# Sensors.net
KiCad netlist of a schematic drawn in Altium Designer
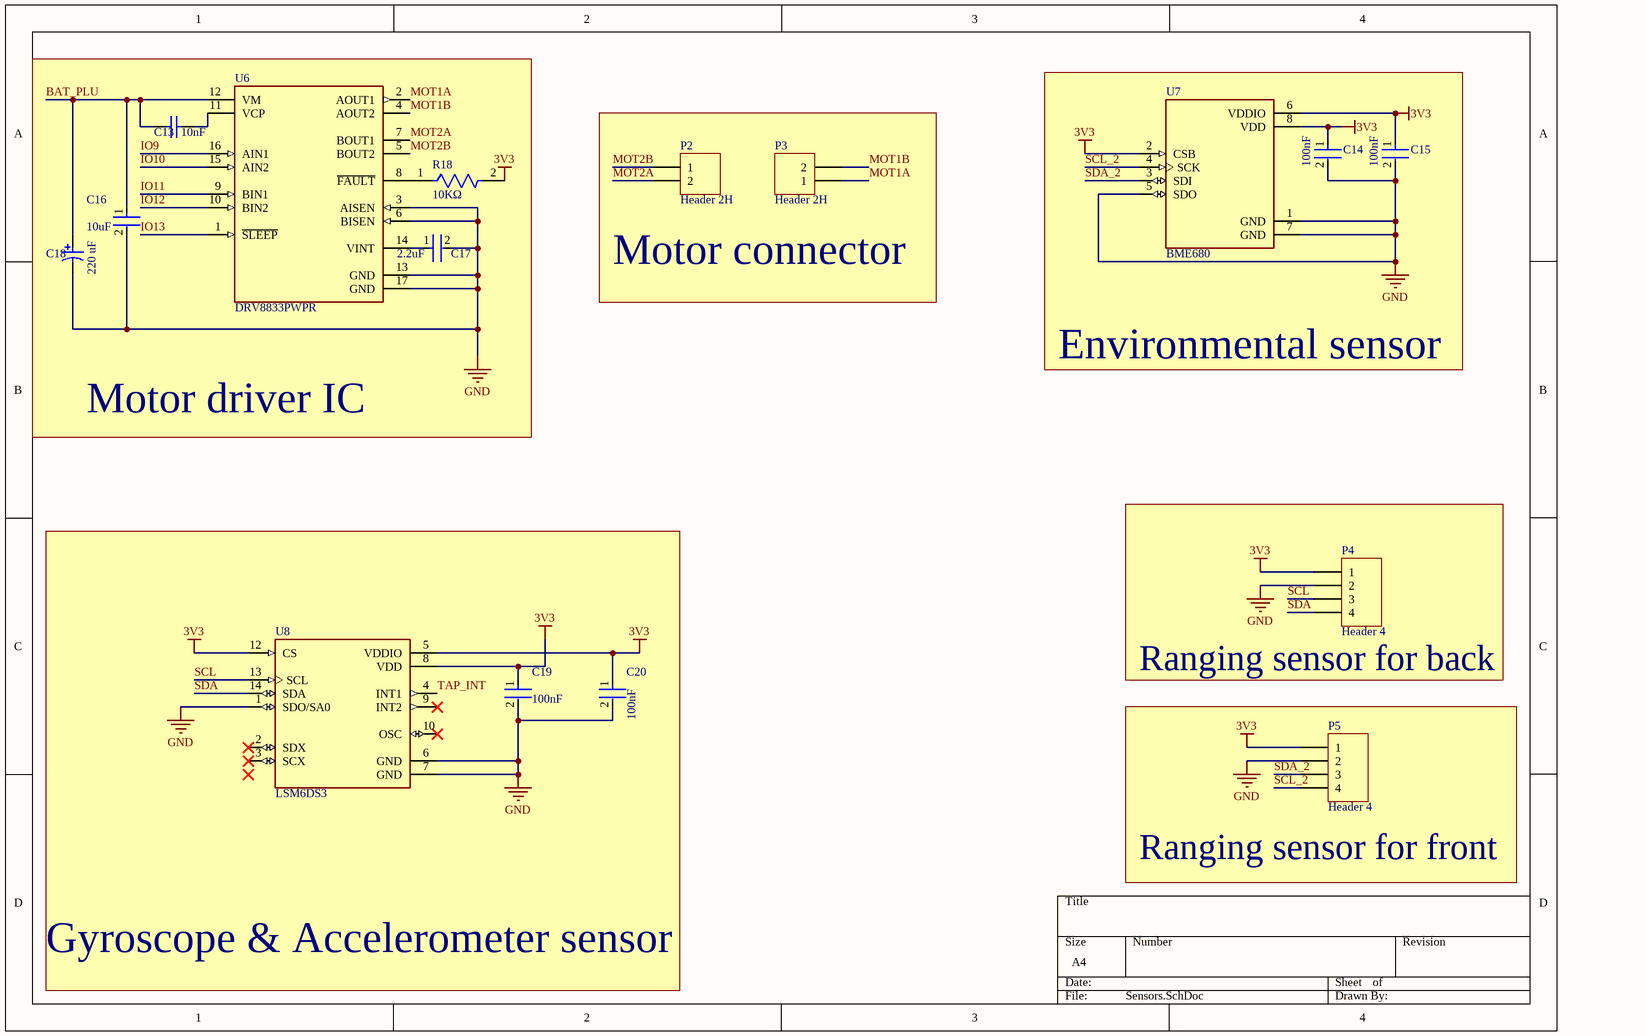
[diagram p0: Sensors.SchDoc]

(export (version "E")
  (design (tool "Eeschema 10.0.6"))
  (components
    (comp (ref "C13")
      (value "10nF")
      (footprint "CAPC0805(2012)145_N")
      (description "CAP 10nF 50V ±10% 0805 (2012 Metric) Thickness 1.45mm SMD")
      (fields (field (name "TOLERANCE") "Â±10%") (field (name "LCSC PART") "C377773"))
      (libsource (lib "Altium Content Vault") (part "CAP"))
    )
    (comp (ref "C14")
      (value "CC0805KKX7RYBB104")
      (footprint "FP-CC0805-EB-IPC_B")
      (description "CC0805KKX7RYBB104 Capacitor Ceramic 0.01uF 250V X7R 10% 0805 T/R")
      (fields
        (field (name "TOLERANCE") "10%")
        (field (name "CAPACITANCE") "100nF")
        (field (name "LCSC PART") "C28233")
      )
      (libsource (lib "Altium Content Vault") (part "b4654b650e69147ec39a6b967a45e02"))
    )
    (comp (ref "C15")
      (value "CC0805KKX7RYBB104")
      (footprint "FP-CC0805-EB-IPC_B")
      (description "CC0805KKX7RYBB104 Capacitor Ceramic 0.01uF 250V X7R 10% 0805 T/R")
      (fields
        (field (name "TOLERANCE") "10%")
        (field (name "CAPACITANCE") "100nF")
        (field (name "LCSC PART") "C28233")
      )
      (libsource (lib "Altium Content Vault") (part "b4654b650e69147ec39a6b967a45e02"))
    )
    (comp (ref "C16")
      (value "C0805C106J8RACAUTO")
      (footprint "FP-C0805C106J8RACAUTO-MFG")
      (description "CAP CER 10UF 10V X7R 0805")
      (fields
        (field (name "CAPACITANCE") "10uF")
        (field (name "TOLERANCE") "5%")
        (field (name "LCSC PART") "C15850")
      )
      (libsource (lib "Altium Content Vault") (part "02cd4be3c70576c341d710602a673aa"))
    )
    (comp (ref "C17")
      (value "08053C225K4Z2A")
      (footprint "FP-0805-L_2_01_0_2-W_1_25-MFG")
      (description "CAP CER 2.2UF 25V X7R 0805")
      (fields
        (field (name "CAPACITANCE") "2.2uF")
        (field (name "TOLERANCE") "10%")
        (field (name "LCSC PART") "C377773")
      )
      (libsource (lib "Altium Content Vault") (part "11868f565c42a9108669ba33697ecf6"))
    )
    (comp (ref "C18")
      (value "UUD1V221MNL1GS")
      (footprint "NIC-CAPA2-8X10_V")
      (fields
        (field (name "RATED CAPACITANCE") "220 uF")
        (field (name "MANUFACTURER") "Nichicon")
        (field (name "LCSC PART") "C2836441")
      )
      (libsource (lib "Altium Content Vault") (part "NIC-CAP-P-2"))
    )
    (comp (ref "C19")
      (value "CC0805KKX7RYBB104")
      (footprint "FP-CC0805-EB-IPC_B")
      (description "CC0805KKX7RYBB104 Capacitor Ceramic 0.01uF 250V X7R 10% 0805 T/R")
      (fields
        (field (name "TOLERANCE") "10%")
        (field (name "CAPACITANCE") "100nF")
        (field (name "LCSC PART") "C28233")
      )
      (libsource (lib "Altium Content Vault") (part "b4654b650e69147ec39a6b967a45e02"))
    )
    (comp (ref "C20")
      (value "CC0805KKX7RYBB104")
      (footprint "FP-CC0805-EB-IPC_B")
      (description "CC0805KKX7RYBB104 Capacitor Ceramic 0.01uF 250V X7R 10% 0805 T/R")
      (fields
        (field (name "TOLERANCE") "10%")
        (field (name "CAPACITANCE") "100nF")
        (field (name "LCSC PART") "C28233")
      )
      (libsource (lib "Altium Content Vault") (part "b4654b650e69147ec39a6b967a45e02"))
    )
    (comp (ref "P2")
      (value "Header 2H")
      (footprint "HDR1X2H")
      (description "Header, 2-Pin, Right Angle")
      (fields (field (name "LCSC PART") "C32713261") (field (name "PUBLISHER") "Altium Limited"))
      (libsource (lib "") (part "Header 2H_1"))
    )
    (comp (ref "P3")
      (value "Header 2H")
      (footprint "HDR1X2H")
      (description "Header, 2-Pin, Right Angle")
      (fields (field (name "LCSC PART") "C32713261") (field (name "PUBLISHER") "Altium Limited"))
      (libsource (lib "Miscellaneous Connectors") (part "Header 2H"))
    )
    (comp (ref "P4")
      (value "Header 4")
      (footprint "HDR1X4")
      (description "Header, 4-Pin")
      (fields (field (name "LCSC PART") "C42431787") (field (name "PUBLISHER") "Altium Limited"))
      (libsource (lib "Miscellaneous Connectors") (part "Header 4"))
    )
    (comp (ref "P5")
      (value "Header 4")
      (footprint "HDR1X4")
      (description "Header, 4-Pin")
      (fields (field (name "LCSC PART") "C42431787") (field (name "PUBLISHER") "Altium Limited"))
      (libsource (lib "Miscellaneous Connectors") (part "Header 4"))
    )
    (comp (ref "R18")
      (value "10KΩ")
      (footprint "FP-RT0805-IPC_B")
      (description "RES SMD 10K OHM 1% 1/8W 0805")
      (fields
        (field (name "OCTOPART") "https://octopart.com/rt0805frd0710kl-yageo-71399701")
        (field (name "TOLERANCE") "0.0001")
      )
      (libsource (lib "Altium Content Vault") (part "1029c3af85768c4190bb7ad29bc67b5"))
    )
    (comp (ref "U6")
      (value "DRV8833PWPR")
      (footprint "FP-PWP0016C-IPC_B")
      (description "IC MOTOR DRIVER PAR 16HTSSOP")
      (fields (field (name "LCSC PART") "C50506"))
      (libsource (lib "Altium Content Vault") (part "bca689d78e207bdabf30b9b31c2f798"))
    )
    (comp (ref "U7")
      (value "BME680")
      (footprint "PSON80P300X300X100-8N")
      (description "Gas, Humidity, Pressure, Temperature Sensor I2C, SPI Output")
      (fields (field (name "MF") "Bosch Sensortec") (field (name "LCSC PART") "C125972"))
      (libsource (lib "BME680") (part "BME680"))
    )
    (comp (ref "U8")
      (value "LSM6DS3")
      (footprint "PQFN50P300X250X86-14N")
      (description "Accelerometer, Gyroscope, Temperature, 6 Axis Sensor IÂ²C, SPI Output")
      (fields (field (name "MF") "STMicroelectronics") (field (name "LCSC PART") "LSM6DS3TR-C"))
      (libsource (lib "LSM6DS3") (part "LSM6DS3"))
    )
  )
  (nets
    (net (code "1") (name "/BAT_PLU") (class "Default")
      (node (ref "C13") (pin "1") (pinfunction "1_1") (pintype "passive"))
      (node (ref "C16") (pin "1") (pinfunction "1_1") (pintype "passive"))
      (node (ref "C18") (pin "1") (pinfunction "1_1") (pintype "passive"))
      (node (ref "U6") (pin "12") (pinfunction "VM_12") (pintype "power_in"))
    )
    (net (code "2") (name "/IO9") (class "Default")
      (node (ref "U6") (pin "16") (pinfunction "AIN1_16") (pintype "input"))
    )
    (net (code "3") (name "/IO10") (class "Default")
      (node (ref "U6") (pin "15") (pinfunction "AIN2_15") (pintype "input"))
    )
    (net (code "4") (name "/IO11") (class "Default")
      (node (ref "U6") (pin "9") (pinfunction "BIN1_9") (pintype "input"))
    )
    (net (code "5") (name "/IO12") (class "Default")
      (node (ref "U6") (pin "10") (pinfunction "BIN2_10") (pintype "input"))
    )
    (net (code "6") (name "/IO13") (class "Default")
      (node (ref "U6") (pin "1") (pinfunction "~{SLEEP}_1") (pintype "input"))
    )
    (net (code "7") (name "/MOT1A") (class "Default")
      (node (ref "P3") (pin "1") (pinfunction "1_1") (pintype "passive"))
      (node (ref "U6") (pin "2") (pinfunction "AOUT1_2") (pintype "output"))
    )
    (net (code "8") (name "/MOT1B") (class "Default")
      (node (ref "P3") (pin "2") (pinfunction "2_2") (pintype "passive"))
      (node (ref "U6") (pin "4") (pinfunction "AOUT2_4") (pintype "tri_state"))
    )
    (net (code "9") (name "/MOT2A") (class "Default")
      (node (ref "P2") (pin "2") (pinfunction "2_2") (pintype "passive"))
      (node (ref "U6") (pin "7") (pinfunction "BOUT1_7") (pintype "tri_state"))
    )
    (net (code "10") (name "/MOT2B") (class "Default")
      (node (ref "P2") (pin "1") (pinfunction "1_1") (pintype "passive"))
      (node (ref "U6") (pin "5") (pinfunction "BOUT2_5") (pintype "tri_state"))
    )
    (net (code "11") (name "/SCL") (class "Default")
      (node (ref "P4") (pin "3") (pinfunction "3_3") (pintype "passive"))
      (node (ref "U8") (pin "13") (pinfunction "SCL_13") (pintype "input"))
    )
    (net (code "12") (name "/SCL_2") (class "Default")
      (node (ref "P5") (pin "4") (pinfunction "4_4") (pintype "passive"))
      (node (ref "U7") (pin "4") (pinfunction "SCK_4") (pintype "input"))
    )
    (net (code "13") (name "/SDA") (class "Default")
      (node (ref "P4") (pin "4") (pinfunction "4_4") (pintype "passive"))
      (node (ref "U8") (pin "14") (pinfunction "SDA_14") (pintype "bidirectional"))
    )
    (net (code "14") (name "/SDA_2") (class "Default")
      (node (ref "P5") (pin "3") (pinfunction "3_3") (pintype "passive"))
      (node (ref "U7") (pin "3") (pinfunction "SDI_3") (pintype "bidirectional"))
    )
    (net (code "15") (name "/TAP_INT") (class "Default")
      (node (ref "U8") (pin "4") (pinfunction "INT1_4") (pintype "output"))
    )
    (net (code "16") (name "3V3") (class "Default")
      (node (ref "C14") (pin "1") (pinfunction "1_1") (pintype "passive"))
      (node (ref "C15") (pin "1") (pinfunction "1_1") (pintype "passive"))
      (node (ref "C19") (pin "1") (pinfunction "1_1") (pintype "passive"))
      (node (ref "C20") (pin "1") (pinfunction "1_1") (pintype "passive"))
      (node (ref "P4") (pin "1") (pinfunction "1_1") (pintype "passive"))
      (node (ref "P5") (pin "1") (pinfunction "1_1") (pintype "passive"))
      (node (ref "R18") (pin "2") (pinfunction "2_2") (pintype "passive"))
      (node (ref "U7") (pin "2") (pinfunction "CSB_2") (pintype "input"))
      (node (ref "U7") (pin "6") (pinfunction "VDDIO_6") (pintype "power_in"))
      (node (ref "U7") (pin "8") (pinfunction "VDD_8") (pintype "power_in"))
      (node (ref "U8") (pin "12") (pinfunction "CS_12") (pintype "input"))
      (node (ref "U8") (pin "5") (pinfunction "VDDIO_5") (pintype "power_in"))
      (node (ref "U8") (pin "8") (pinfunction "VDD_8") (pintype "power_in"))
    )
    (net (code "17") (name "GND") (class "Default")
      (node (ref "C14") (pin "2") (pinfunction "2_2") (pintype "passive"))
      (node (ref "C15") (pin "2") (pinfunction "2_2") (pintype "passive"))
      (node (ref "C16") (pin "2") (pinfunction "2_2") (pintype "passive"))
      (node (ref "C17") (pin "2") (pinfunction "2_2") (pintype "passive"))
      (node (ref "C18") (pin "2") (pinfunction "2_2") (pintype "passive"))
      (node (ref "C19") (pin "2") (pinfunction "2_2") (pintype "passive"))
      (node (ref "C20") (pin "2") (pinfunction "2_2") (pintype "passive"))
      (node (ref "P4") (pin "2") (pinfunction "2_2") (pintype "passive"))
      (node (ref "P5") (pin "2") (pinfunction "2_2") (pintype "passive"))
      (node (ref "U6") (pin "13") (pinfunction "GND_13") (pintype "power_in"))
      (node (ref "U6") (pin "17") (pinfunction "GND_17") (pintype "power_in"))
      (node (ref "U6") (pin "3") (pinfunction "AISEN_3") (pintype "input"))
      (node (ref "U6") (pin "6") (pinfunction "BISEN_6") (pintype "input"))
      (node (ref "U7") (pin "1") (pinfunction "GND_1") (pintype "power_in"))
      (node (ref "U7") (pin "5") (pinfunction "SDO_5") (pintype "bidirectional"))
      (node (ref "U7") (pin "7") (pinfunction "GND_7") (pintype "power_in"))
      (node (ref "U8") (pin "1") (pinfunction "SDO/SA0_1") (pintype "bidirectional"))
      (node (ref "U8") (pin "6") (pinfunction "GND_6") (pintype "power_in"))
      (node (ref "U8") (pin "7") (pinfunction "GND_7") (pintype "power_in"))
    )
    (net (code "18") (name "Net-(U6-VCP)") (class "Default")
      (node (ref "C13") (pin "2") (pinfunction "2_2") (pintype "passive"))
      (node (ref "U6") (pin "11") (pinfunction "VCP_11") (pintype "passive"))
    )
    (net (code "19") (name "Net-(U6-VINT)") (class "Default")
      (node (ref "C17") (pin "1") (pinfunction "1_1") (pintype "passive"))
      (node (ref "U6") (pin "14") (pinfunction "VINT_14") (pintype "power_in"))
    )
    (net (code "20") (name "Net-(U6-~{FAULT})") (class "Default")
      (node (ref "R18") (pin "1") (pinfunction "1_1") (pintype "passive"))
      (node (ref "U6") (pin "8") (pinfunction "~{FAULT}_8") (pintype "open_collector"))
    )
    (net (code "21") (name "unconnected-(U8-INT2-Pad9)") (class "Default")
      (node (ref "U8") (pin "9") (pinfunction "INT2_9") (pintype "output+no_connect"))
    )
    (net (code "22") (name "unconnected-(U8-OSC-Pad10)") (class "Default")
      (node (ref "U8") (pin "10") (pinfunction "OSC_10") (pintype "bidirectional+no_connect"))
    )
    (net (code "23") (name "unconnected-(U8-SCX-Pad3)") (class "Default")
      (node (ref "U8") (pin "3") (pinfunction "SCX_3") (pintype "bidirectional+no_connect"))
    )
    (net (code "24") (name "unconnected-(U8-SDX-Pad2)") (class "Default")
      (node (ref "U8") (pin "2") (pinfunction "SDX_2") (pintype "bidirectional+no_connect"))
    )
  )
)
